# Sh.net
KiCad netlist of a schematic drawn in Altium Designer
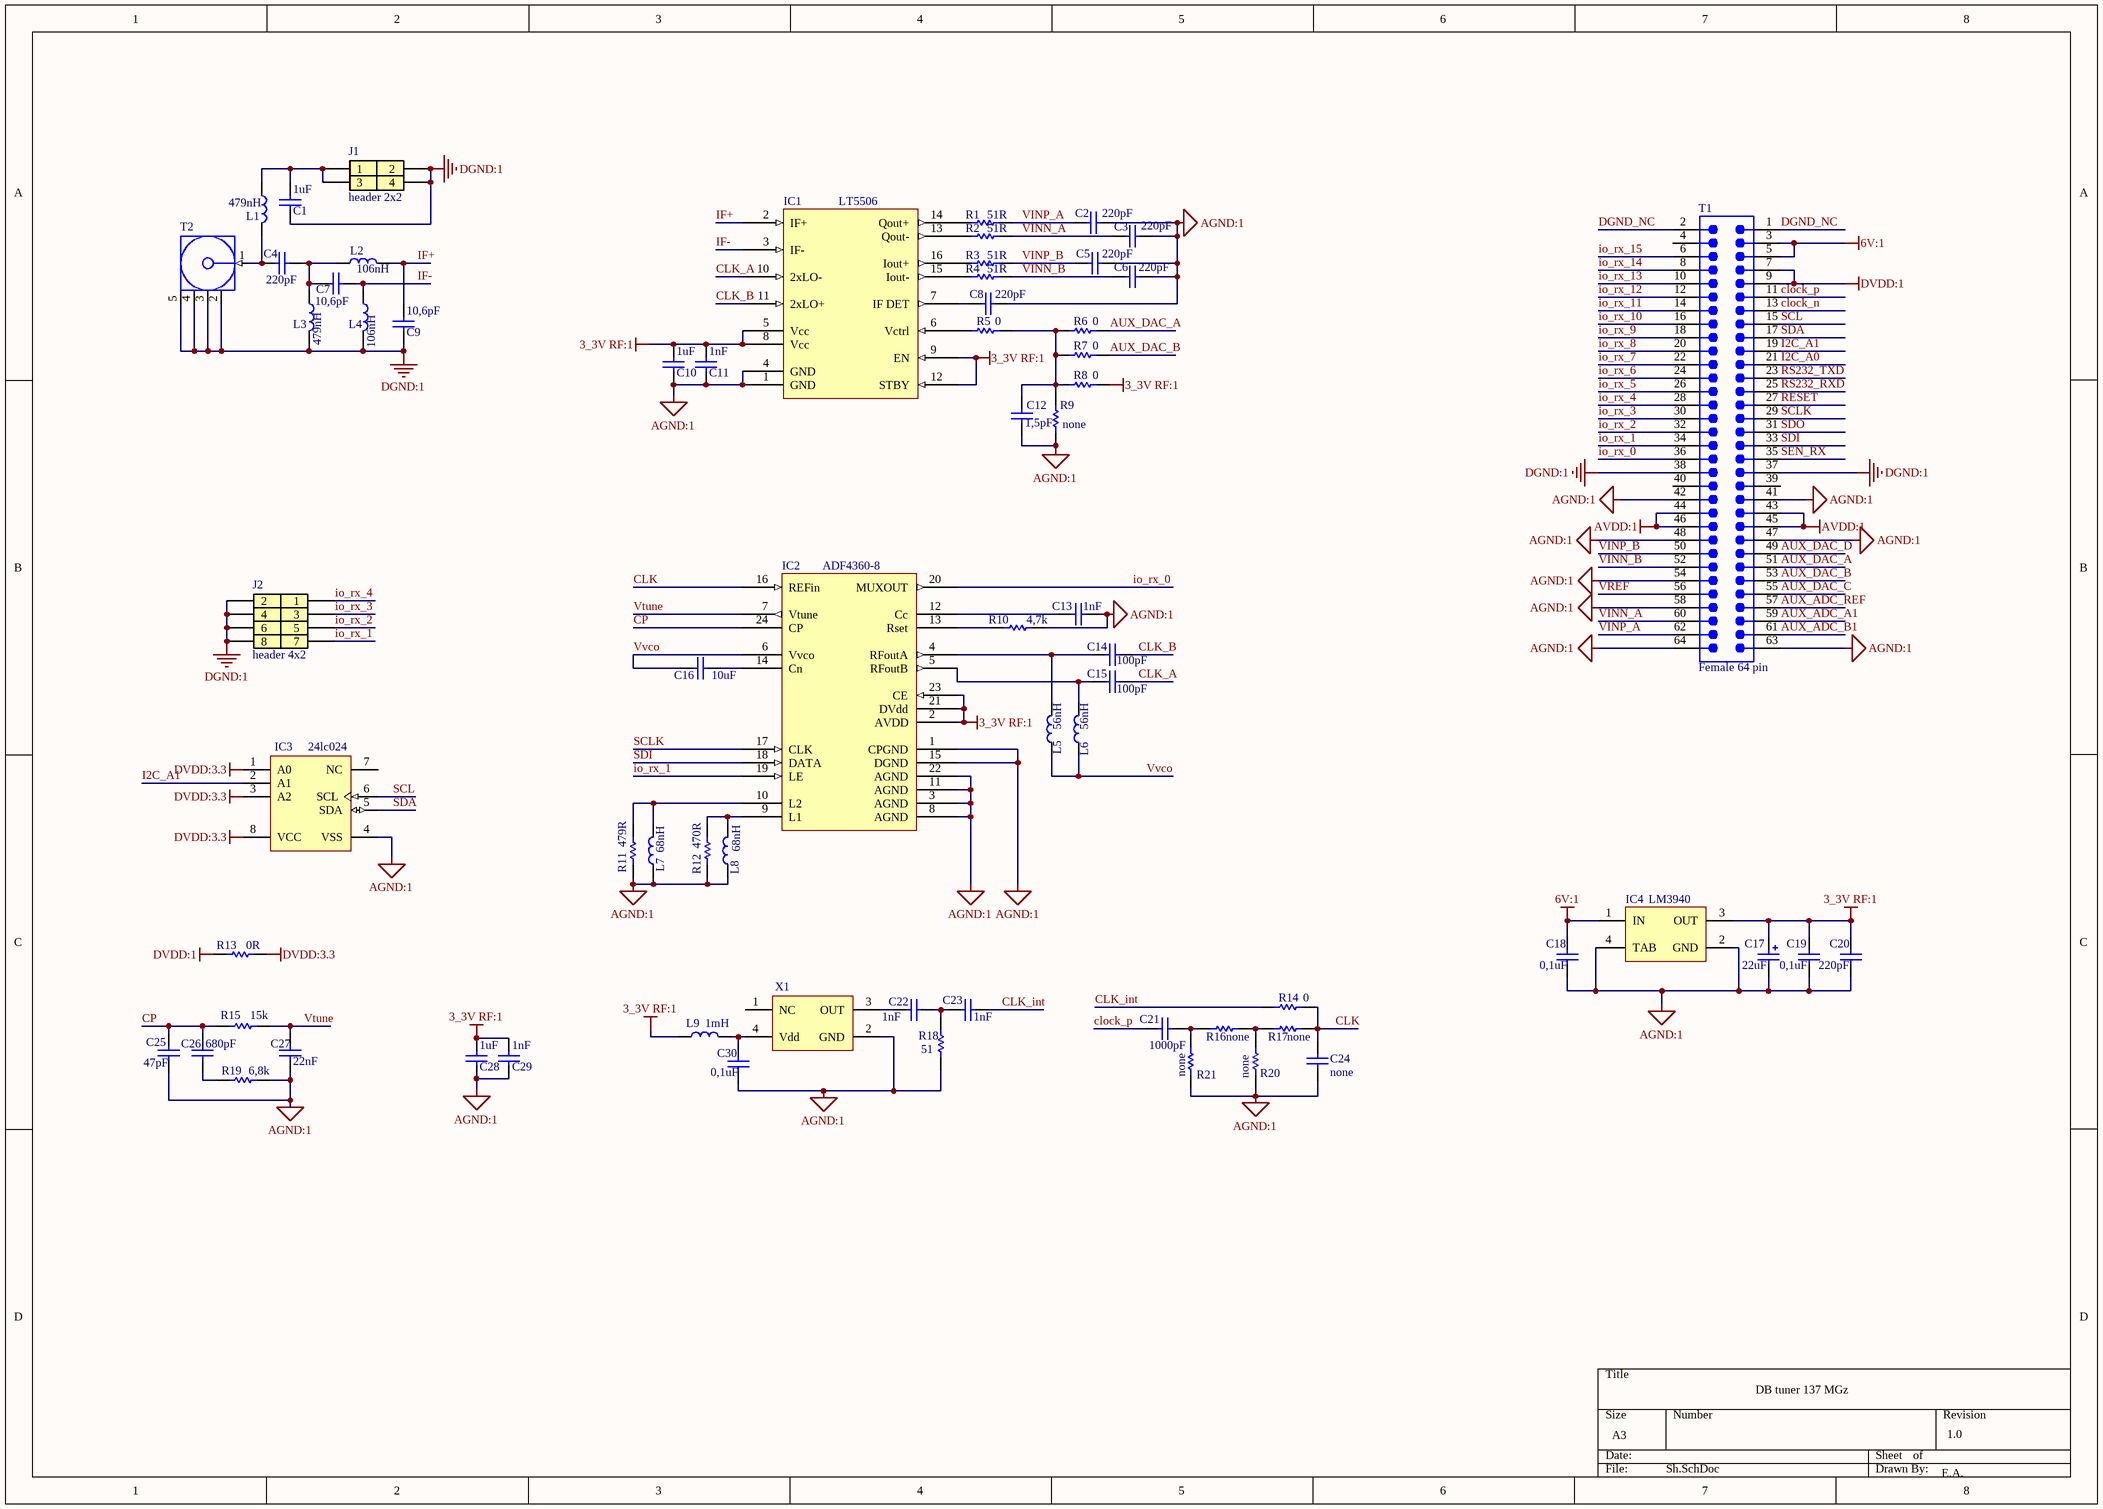
[diagram p0: Sh.SchDoc]

(export (version "E")
  (design (tool "Eeschema 10.0.6"))
  (components
    (comp (ref "C1") (value "1uF") (footprint "0805 cap") (libsource (lib "DB") (part "ceramic capacitor")))
    (comp (ref "C2") (value "220pF") (footprint "0805 cap") (libsource (lib "DB") (part "ceramic capacitor")))
    (comp (ref "C3") (value "220pF") (footprint "0805 cap") (libsource (lib "DB") (part "ceramic capacitor")))
    (comp (ref "C4") (value "220pF") (footprint "0805 cap") (libsource (lib "DB") (part "ceramic capacitor")))
    (comp (ref "C5") (value "220pF") (footprint "0805 cap") (libsource (lib "DB") (part "ceramic capacitor")))
    (comp (ref "C6") (value "220pF") (footprint "0805 cap") (libsource (lib "DB") (part "ceramic capacitor")))
    (comp (ref "C7")
      (value "10,6pF")
      (footprint "0805 cap")
      (libsource (lib "DB") (part "ceramic capacitor"))
    )
    (comp (ref "C8") (value "220pF") (footprint "0805 cap") (libsource (lib "DB") (part "ceramic capacitor")))
    (comp (ref "C9")
      (value "10,6pF")
      (footprint "0805 cap")
      (libsource (lib "DB") (part "ceramic capacitor"))
    )
    (comp (ref "C10") (value "1uF") (footprint "0805 cap") (libsource (lib "DB") (part "ceramic capacitor")))
    (comp (ref "C11") (value "1nF") (footprint "0805 cap") (libsource (lib "DB") (part "ceramic capacitor")))
    (comp (ref "C12")
      (value "1,5pF")
      (footprint "0805 cap")
      (libsource (lib "DB") (part "ceramic capacitor"))
    )
    (comp (ref "C13") (value "1nF") (footprint "0805 cap") (libsource (lib "DB") (part "ceramic capacitor")))
    (comp (ref "C14")
      (value "100pF")
      (footprint "0805 cap")
      (libsource (lib "DB") (part "ceramic capacitor"))
    )
    (comp (ref "C15")
      (value "100pF")
      (footprint "0805 cap")
      (libsource (lib "DB") (part "ceramic capacitor"))
    )
    (comp (ref "C16") (value "10uF") (footprint "0805 cap") (libsource (lib "DB") (part "ceramic capacitor")))
    (comp (ref "C17")
      (value "22uF")
      (footprint "capacitor C")
      (libsource (lib "DB") (part "tantalum capacitor"))
    )
    (comp (ref "C18")
      (value "0,1uF")
      (footprint "0805 cap")
      (libsource (lib "DB") (part "ceramic capacitor"))
    )
    (comp (ref "C19")
      (value "0,1uF")
      (footprint "0805 cap")
      (libsource (lib "DB") (part "ceramic capacitor"))
    )
    (comp (ref "C20")
      (value "220pF")
      (footprint "0805 cap")
      (libsource (lib "DB") (part "ceramic capacitor"))
    )
    (comp (ref "C21")
      (value "1000pF")
      (footprint "0805 cap")
      (libsource (lib "DB") (part "ceramic capacitor"))
    )
    (comp (ref "C22") (value "1nF") (footprint "0805 cap") (libsource (lib "DB") (part "ceramic capacitor")))
    (comp (ref "C23") (value "1nF") (footprint "0805 cap") (libsource (lib "DB") (part "ceramic capacitor")))
    (comp (ref "C24") (value "none") (footprint "0805 cap") (libsource (lib "DB") (part "ceramic capacitor")))
    (comp (ref "C25") (value "47pF") (footprint "0805 cap") (libsource (lib "DB") (part "ceramic capacitor")))
    (comp (ref "C26")
      (value "680pF")
      (footprint "0805 cap")
      (libsource (lib "DB") (part "ceramic capacitor"))
    )
    (comp (ref "C27") (value "22nF") (footprint "0805 cap") (libsource (lib "DB") (part "ceramic capacitor")))
    (comp (ref "C28") (value "1uF") (footprint "0805 cap") (libsource (lib "DB") (part "ceramic capacitor")))
    (comp (ref "C29") (value "1nF") (footprint "0805 cap") (libsource (lib "DB") (part "ceramic capacitor")))
    (comp (ref "C30")
      (value "0,1uF")
      (footprint "0805 cap")
      (libsource (lib "DB") (part "ceramic capacitor"))
    )
    (comp (ref "IC1")
      (value "LT5506")
      (footprint "QFN65P400X400X80-16N")
      (description "40MHz to 500MHz  Quadrature Demodulator  with VGA")
      (libsource (lib "DB") (part "LT5506"))
    )
    (comp (ref "IC2")
      (value "ADF4360-8")
      (footprint "QFN50P408X408X100-24N")
      (description "Integrated Synthesizer and VCO")
      (libsource (lib "DB") (part "ADF4360-8"))
    )
    (comp (ref "IC3") (value "24lc024") (footprint "SOIC_SN8") (libsource (lib "DB") (part "24lc024")))
    (comp (ref "IC4") (value "LM3940") (footprint "TO-263") (libsource (lib "DB") (part "LM3940")))
    (comp (ref "J1") (value "header 2x2") (footprint "pld 2x2") (libsource (lib "DB") (part "header 2x2")))
    (comp (ref "J2") (value "header 4x2") (footprint "H_4x2") (libsource (lib "DB") (part "header 4x2")))
    (comp (ref "L1") (value "479nH") (footprint "inductor 0805") (libsource (lib "DB") (part "inductor")))
    (comp (ref "L2") (value "106nH") (footprint "inductor 0805") (libsource (lib "") (part "inductor_1")))
    (comp (ref "L3") (value "479nH") (footprint "inductor 0805") (libsource (lib "DB") (part "inductor")))
    (comp (ref "L4") (value "106nH") (footprint "inductor 0805") (libsource (lib "DB") (part "inductor")))
    (comp (ref "L5") (value "56nH") (footprint "inductor 0805") (libsource (lib "DB") (part "inductor")))
    (comp (ref "L6") (value "56nH") (footprint "inductor 0805") (libsource (lib "DB") (part "inductor")))
    (comp (ref "L7") (value "68nH") (footprint "inductor 0805") (libsource (lib "DB") (part "inductor")))
    (comp (ref "L8") (value "68nH") (footprint "inductor 0805") (libsource (lib "DB") (part "inductor")))
    (comp (ref "L9") (value "1mH") (footprint "inductor 0805") (libsource (lib "") (part "inductor_1")))
    (comp (ref "R1") (value "51R") (footprint "0805 resistor") (libsource (lib "DB") (part "resistor")))
    (comp (ref "R2") (value "51R") (footprint "0805 resistor") (libsource (lib "DB") (part "resistor")))
    (comp (ref "R3") (value "51R") (footprint "0805 resistor") (libsource (lib "DB") (part "resistor")))
    (comp (ref "R4") (value "51R") (footprint "0805 resistor") (libsource (lib "DB") (part "resistor")))
    (comp (ref "R5") (value "0") (footprint "0805 resistor") (libsource (lib "DB") (part "resistor")))
    (comp (ref "R6") (value "0") (footprint "0805 resistor") (libsource (lib "DB") (part "resistor")))
    (comp (ref "R7") (value "0") (footprint "0805 resistor") (libsource (lib "DB") (part "resistor")))
    (comp (ref "R8") (value "0") (footprint "0805 resistor") (libsource (lib "DB") (part "resistor")))
    (comp (ref "R9") (value "none") (footprint "0805 resistor") (libsource (lib "DB") (part "resistor")))
    (comp (ref "R10") (value "4,7k") (footprint "0805 resistor") (libsource (lib "DB") (part "resistor")))
    (comp (ref "R11") (value "479R") (footprint "0805 resistor") (libsource (lib "DB") (part "resistor")))
    (comp (ref "R12") (value "470R") (footprint "0805 resistor") (libsource (lib "DB") (part "resistor")))
    (comp (ref "R13") (value "0R") (footprint "0805 resistor") (libsource (lib "DB") (part "resistor")))
    (comp (ref "R14") (value "0") (footprint "0805 resistor") (libsource (lib "DB") (part "resistor")))
    (comp (ref "R15") (value "15k") (footprint "0805 resistor") (libsource (lib "DB") (part "resistor")))
    (comp (ref "R16") (value "none") (footprint "0805 resistor") (libsource (lib "DB") (part "resistor")))
    (comp (ref "R17") (value "none") (footprint "0805 resistor") (libsource (lib "DB") (part "resistor")))
    (comp (ref "R18") (value "51") (footprint "0805 resistor") (libsource (lib "DB") (part "resistor")))
    (comp (ref "R19") (value "6,8k") (footprint "0805 resistor") (libsource (lib "DB") (part "resistor")))
    (comp (ref "R20") (value "none") (footprint "0805 resistor") (libsource (lib "DB") (part "resistor")))
    (comp (ref "R21") (value "none") (footprint "0805 resistor") (libsource (lib "DB") (part "resistor")))
    (comp (ref "T1")
      (value "Female 64 pin")
      (footprint "64pin female Mezzanine")
      (libsource (lib "DB") (part "Female 64 pin"))
    )
    (comp (ref "T2") (value "mcx_connect") (footprint "mcx_ra") (libsource (lib "DB") (part "mcx_connect")))
    (comp (ref "X1") (value "vcxo") (footprint "CLOCK OSCILLATOR") (libsource (lib "DB") (part "vcxo")))
  )
  (nets
    (net (code "1") (name "/AUX_ADC_A1") (class "Default")
      (node (ref "T1") (pin "59") (pinfunction "59_59") (pintype "passive"))
    )
    (net (code "2") (name "/AUX_ADC_B1") (class "Default")
      (node (ref "T1") (pin "61") (pinfunction "61_61") (pintype "passive"))
    )
    (net (code "3") (name "/AUX_ADC_REF") (class "Default")
      (node (ref "T1") (pin "57") (pinfunction "57_57") (pintype "passive"))
    )
    (net (code "4") (name "/AUX_DAC_A") (class "Default")
      (node (ref "R6") (pin "2") (pinfunction "2_2") (pintype "passive"))
      (node (ref "T1") (pin "51") (pinfunction "51_51") (pintype "passive"))
    )
    (net (code "5") (name "/AUX_DAC_B") (class "Default")
      (node (ref "R7") (pin "2") (pinfunction "2_2") (pintype "passive"))
      (node (ref "T1") (pin "53") (pinfunction "53_53") (pintype "passive"))
    )
    (net (code "6") (name "/AUX_DAC_C") (class "Default")
      (node (ref "T1") (pin "55") (pinfunction "55_55") (pintype "passive"))
    )
    (net (code "7") (name "/AUX_DAC_D") (class "Default")
      (node (ref "T1") (pin "49") (pinfunction "49_49") (pintype "passive"))
    )
    (net (code "8") (name "/CLK") (class "Default")
      (node (ref "C24") (pin "2") (pinfunction "2_2") (pintype "passive"))
      (node (ref "IC2") (pin "16") (pinfunction "REFin_16") (pintype "input"))
      (node (ref "R14") (pin "2") (pinfunction "2_2") (pintype "passive"))
      (node (ref "R17") (pin "1") (pinfunction "1_1") (pintype "passive"))
    )
    (net (code "9") (name "/CLK_A") (class "Default")
      (node (ref "C15") (pin "1") (pinfunction "1_1") (pintype "passive"))
      (node (ref "IC1") (pin "10") (pinfunction "2xLO-_10") (pintype "input"))
    )
    (net (code "10") (name "/CLK_B") (class "Default")
      (node (ref "C14") (pin "1") (pinfunction "1_1") (pintype "passive"))
      (node (ref "IC1") (pin "11") (pinfunction "2xLO+_11") (pintype "input"))
    )
    (net (code "11") (name "/CLK_int") (class "Default")
      (node (ref "C23") (pin "2") (pinfunction "2_2") (pintype "passive"))
      (node (ref "R14") (pin "1") (pinfunction "1_1") (pintype "passive"))
    )
    (net (code "12") (name "/CP") (class "Default")
      (node (ref "C25") (pin "2") (pinfunction "2_2") (pintype "passive"))
      (node (ref "C26") (pin "2") (pinfunction "2_2") (pintype "passive"))
      (node (ref "IC2") (pin "24") (pinfunction "CP_24") (pintype "passive"))
      (node (ref "R15") (pin "1") (pinfunction "1_1") (pintype "passive"))
    )
    (net (code "13") (name "/DGND_NC") (class "Default")
      (node (ref "T1") (pin "1") (pinfunction "1_1") (pintype "passive"))
      (node (ref "T1") (pin "2") (pinfunction "2_2") (pintype "passive"))
    )
    (net (code "14") (name "/I2C_A0") (class "Default")
      (node (ref "T1") (pin "21") (pinfunction "21_21") (pintype "passive"))
    )
    (net (code "15") (name "/I2C_A1") (class "Default")
      (node (ref "IC3") (pin "2") (pinfunction "A1_2") (pintype "passive"))
      (node (ref "T1") (pin "19") (pinfunction "19_19") (pintype "passive"))
    )
    (net (code "16") (name "/IF+") (class "Default")
      (node (ref "C9") (pin "2") (pinfunction "2_2") (pintype "passive"))
      (node (ref "IC1") (pin "2") (pinfunction "IF+_2") (pintype "input"))
      (node (ref "L2") (pin "2") (pinfunction "2_2") (pintype "passive"))
    )
    (net (code "17") (name "/IF-") (class "Default")
      (node (ref "C7") (pin "2") (pinfunction "2_2") (pintype "passive"))
      (node (ref "IC1") (pin "3") (pinfunction "IF-_3") (pintype "input"))
      (node (ref "L4") (pin "1") (pinfunction "1_1") (pintype "passive"))
    )
    (net (code "18") (name "/RESET") (class "Default")
      (node (ref "T1") (pin "27") (pinfunction "27_27") (pintype "passive"))
    )
    (net (code "19") (name "/RS232_RXD") (class "Default")
      (node (ref "T1") (pin "25") (pinfunction "25_25") (pintype "passive"))
    )
    (net (code "20") (name "/RS232_TXD") (class "Default")
      (node (ref "T1") (pin "23") (pinfunction "23_23") (pintype "passive"))
    )
    (net (code "21") (name "/SCL") (class "Default")
      (node (ref "IC3") (pin "6") (pinfunction "SCL_6") (pintype "input"))
      (node (ref "T1") (pin "15") (pinfunction "15_15") (pintype "passive"))
    )
    (net (code "22") (name "/SCLK") (class "Default")
      (node (ref "IC2") (pin "17") (pinfunction "CLK_17") (pintype "input"))
      (node (ref "T1") (pin "29") (pinfunction "29_29") (pintype "passive"))
    )
    (net (code "23") (name "/SDA") (class "Default")
      (node (ref "IC3") (pin "5") (pinfunction "SDA_5") (pintype "bidirectional"))
      (node (ref "T1") (pin "17") (pinfunction "17_17") (pintype "passive"))
    )
    (net (code "24") (name "/SDI") (class "Default")
      (node (ref "IC2") (pin "18") (pinfunction "DATA_18") (pintype "input"))
      (node (ref "T1") (pin "33") (pinfunction "33_33") (pintype "passive"))
    )
    (net (code "25") (name "/SDO") (class "Default")
      (node (ref "T1") (pin "31") (pinfunction "31_31") (pintype "passive"))
    )
    (net (code "26") (name "/SEN_RX") (class "Default")
      (node (ref "T1") (pin "35") (pinfunction "35_35") (pintype "passive"))
    )
    (net (code "27") (name "/VINN_A") (class "Default")
      (node (ref "C3") (pin "1") (pinfunction "1_1") (pintype "passive"))
      (node (ref "R2") (pin "2") (pinfunction "2_2") (pintype "passive"))
      (node (ref "T1") (pin "60") (pinfunction "60_60") (pintype "passive"))
    )
    (net (code "28") (name "/VINN_B") (class "Default")
      (node (ref "C6") (pin "1") (pinfunction "1_1") (pintype "passive"))
      (node (ref "R4") (pin "2") (pinfunction "2_2") (pintype "passive"))
      (node (ref "T1") (pin "52") (pinfunction "52_52") (pintype "passive"))
    )
    (net (code "29") (name "/VINP_A") (class "Default")
      (node (ref "C2") (pin "1") (pinfunction "1_1") (pintype "passive"))
      (node (ref "R1") (pin "2") (pinfunction "2_2") (pintype "passive"))
      (node (ref "T1") (pin "62") (pinfunction "62_62") (pintype "passive"))
    )
    (net (code "30") (name "/VINP_B") (class "Default")
      (node (ref "C5") (pin "1") (pinfunction "1_1") (pintype "passive"))
      (node (ref "R3") (pin "2") (pinfunction "2_2") (pintype "passive"))
      (node (ref "T1") (pin "50") (pinfunction "50_50") (pintype "passive"))
    )
    (net (code "31") (name "/VREF") (class "Default")
      (node (ref "T1") (pin "56") (pinfunction "56_56") (pintype "passive"))
    )
    (net (code "32") (name "/Vtune") (class "Default")
      (node (ref "C27") (pin "2") (pinfunction "2_2") (pintype "passive"))
      (node (ref "IC2") (pin "7") (pinfunction "Vtune_7") (pintype "output"))
      (node (ref "R15") (pin "2") (pinfunction "2_2") (pintype "passive"))
    )
    (net (code "33") (name "/Vvco") (class "Default")
      (node (ref "C16") (pin "1") (pinfunction "1_1") (pintype "passive"))
      (node (ref "IC2") (pin "6") (pinfunction "Vvco_6") (pintype "power_in"))
      (node (ref "L5") (pin "1") (pinfunction "1_1") (pintype "passive"))
      (node (ref "L6") (pin "1") (pinfunction "1_1") (pintype "passive"))
    )
    (net (code "34") (name "/clock_n") (class "Default")
      (node (ref "T1") (pin "13") (pinfunction "13_13") (pintype "passive"))
    )
    (net (code "35") (name "/clock_p") (class "Default")
      (node (ref "C21") (pin "1") (pinfunction "1_1") (pintype "passive"))
      (node (ref "T1") (pin "11") (pinfunction "11_11") (pintype "passive"))
    )
    (net (code "36") (name "/io_rx_0") (class "Default")
      (node (ref "IC2") (pin "20") (pinfunction "MUXOUT_20") (pintype "output"))
      (node (ref "T1") (pin "36") (pinfunction "36_36") (pintype "passive"))
    )
    (net (code "37") (name "/io_rx_1") (class "Default")
      (node (ref "IC2") (pin "19") (pinfunction "LE_19") (pintype "input"))
      (node (ref "J2") (pin "7") (pinfunction "7_7") (pintype "passive"))
      (node (ref "T1") (pin "34") (pinfunction "34_34") (pintype "passive"))
    )
    (net (code "38") (name "/io_rx_2") (class "Default")
      (node (ref "J2") (pin "5") (pinfunction "5_5") (pintype "passive"))
      (node (ref "T1") (pin "32") (pinfunction "32_32") (pintype "passive"))
    )
    (net (code "39") (name "/io_rx_3") (class "Default")
      (node (ref "J2") (pin "3") (pinfunction "3_3") (pintype "passive"))
      (node (ref "T1") (pin "30") (pinfunction "30_30") (pintype "passive"))
    )
    (net (code "40") (name "/io_rx_4") (class "Default")
      (node (ref "J2") (pin "1") (pinfunction "1_1") (pintype "passive"))
      (node (ref "T1") (pin "28") (pinfunction "28_28") (pintype "passive"))
    )
    (net (code "41") (name "/io_rx_5") (class "Default")
      (node (ref "T1") (pin "26") (pinfunction "26_26") (pintype "passive"))
    )
    (net (code "42") (name "/io_rx_6") (class "Default")
      (node (ref "T1") (pin "24") (pinfunction "24_24") (pintype "passive"))
    )
    (net (code "43") (name "/io_rx_7") (class "Default")
      (node (ref "T1") (pin "22") (pinfunction "22_22") (pintype "passive"))
    )
    (net (code "44") (name "/io_rx_8") (class "Default")
      (node (ref "T1") (pin "20") (pinfunction "20_20") (pintype "passive"))
    )
    (net (code "45") (name "/io_rx_9") (class "Default")
      (node (ref "T1") (pin "18") (pinfunction "18_18") (pintype "passive"))
    )
    (net (code "46") (name "/io_rx_10") (class "Default")
      (node (ref "T1") (pin "16") (pinfunction "16_16") (pintype "passive"))
    )
    (net (code "47") (name "/io_rx_11") (class "Default")
      (node (ref "T1") (pin "14") (pinfunction "14_14") (pintype "passive"))
    )
    (net (code "48") (name "/io_rx_12") (class "Default")
      (node (ref "T1") (pin "12") (pinfunction "12_12") (pintype "passive"))
    )
    (net (code "49") (name "/io_rx_13") (class "Default")
      (node (ref "T1") (pin "10") (pinfunction "10_10") (pintype "passive"))
    )
    (net (code "50") (name "/io_rx_14") (class "Default")
      (node (ref "T1") (pin "8") (pinfunction "8_8") (pintype "passive"))
    )
    (net (code "51") (name "/io_rx_15") (class "Default")
      (node (ref "T1") (pin "6") (pinfunction "6_6") (pintype "passive"))
    )
    (net (code "52") (name "3_3V RF:1") (class "Default")
      (node (ref "C10") (pin "2") (pinfunction "2_2") (pintype "passive"))
      (node (ref "C11") (pin "2") (pinfunction "2_2") (pintype "passive"))
      (node (ref "C17") (pin "1") (pinfunction "1_1") (pintype "passive"))
      (node (ref "C19") (pin "2") (pinfunction "2_2") (pintype "passive"))
      (node (ref "C20") (pin "2") (pinfunction "2_2") (pintype "passive"))
      (node (ref "C28") (pin "2") (pinfunction "2_2") (pintype "passive"))
      (node (ref "C29") (pin "2") (pinfunction "2_2") (pintype "passive"))
      (node (ref "IC1") (pin "12") (pinfunction "STBY_12") (pintype "input"))
      (node (ref "IC1") (pin "5") (pinfunction "Vcc_5") (pintype "power_in"))
      (node (ref "IC1") (pin "8") (pinfunction "Vcc_8") (pintype "power_in"))
      (node (ref "IC1") (pin "9") (pinfunction "EN_9") (pintype "input"))
      (node (ref "IC2") (pin "2") (pinfunction "AVDD_2") (pintype "power_in"))
      (node (ref "IC2") (pin "21") (pinfunction "DVdd_21") (pintype "power_in"))
      (node (ref "IC2") (pin "23") (pinfunction "CE_23") (pintype "input"))
      (node (ref "IC4") (pin "3") (pinfunction "OUT_3") (pintype "power_in"))
      (node (ref "L9") (pin "1") (pinfunction "1_1") (pintype "passive"))
      (node (ref "R8") (pin "2") (pinfunction "2_2") (pintype "passive"))
    )
    (net (code "53") (name "6V:1") (class "Default")
      (node (ref "C18") (pin "1") (pinfunction "1_1") (pintype "passive"))
      (node (ref "IC4") (pin "1") (pinfunction "IN_1") (pintype "power_in"))
      (node (ref "T1") (pin "3") (pinfunction "3_3") (pintype "passive"))
      (node (ref "T1") (pin "5") (pinfunction "5_5") (pintype "passive"))
    )
    (net (code "54") (name "AGND:1") (class "Default")
      (node (ref "C10") (pin "1") (pinfunction "1_1") (pintype "passive"))
      (node (ref "C11") (pin "1") (pinfunction "1_1") (pintype "passive"))
      (node (ref "C12") (pin "1") (pinfunction "1_1") (pintype "passive"))
      (node (ref "C13") (pin "1") (pinfunction "1_1") (pintype "passive"))
      (node (ref "C17") (pin "2") (pinfunction "2_2") (pintype "passive"))
      (node (ref "C18") (pin "2") (pinfunction "2_2") (pintype "passive"))
      (node (ref "C19") (pin "1") (pinfunction "1_1") (pintype "passive"))
      (node (ref "C2") (pin "2") (pinfunction "2_2") (pintype "passive"))
      (node (ref "C20") (pin "1") (pinfunction "1_1") (pintype "passive"))
      (node (ref "C24") (pin "1") (pinfunction "1_1") (pintype "passive"))
      (node (ref "C25") (pin "1") (pinfunction "1_1") (pintype "passive"))
      (node (ref "C27") (pin "1") (pinfunction "1_1") (pintype "passive"))
      (node (ref "C28") (pin "1") (pinfunction "1_1") (pintype "passive"))
      (node (ref "C29") (pin "1") (pinfunction "1_1") (pintype "passive"))
      (node (ref "C3") (pin "2") (pinfunction "2_2") (pintype "passive"))
      (node (ref "C30") (pin "1") (pinfunction "1_1") (pintype "passive"))
      (node (ref "C5") (pin "2") (pinfunction "2_2") (pintype "passive"))
      (node (ref "C6") (pin "2") (pinfunction "2_2") (pintype "passive"))
      (node (ref "C8") (pin "2") (pinfunction "2_2") (pintype "passive"))
      (node (ref "IC1") (pin "1") (pinfunction "GND_1") (pintype "power_in"))
      (node (ref "IC1") (pin "4") (pinfunction "GND_4") (pintype "power_in"))
      (node (ref "IC2") (pin "1") (pinfunction "CPGND_1") (pintype "power_in"))
      (node (ref "IC2") (pin "11") (pinfunction "AGND_11") (pintype "power_in"))
      (node (ref "IC2") (pin "15") (pinfunction "DGND_15") (pintype "power_in"))
      (node (ref "IC2") (pin "22") (pinfunction "AGND_22") (pintype "power_in"))
      (node (ref "IC2") (pin "3") (pinfunction "AGND_3") (pintype "power_in"))
      (node (ref "IC2") (pin "8") (pinfunction "AGND_8") (pintype "power_in"))
      (node (ref "IC3") (pin "4") (pinfunction "VSS_4") (pintype "power_in"))
      (node (ref "IC4") (pin "2") (pinfunction "GND_2") (pintype "power_in"))
      (node (ref "IC4") (pin "4") (pinfunction "TAB_4") (pintype "power_in"))
      (node (ref "L7") (pin "1") (pinfunction "1_1") (pintype "passive"))
      (node (ref "L8") (pin "1") (pinfunction "1_1") (pintype "passive"))
      (node (ref "R10") (pin "2") (pinfunction "2_2") (pintype "passive"))
      (node (ref "R11") (pin "1") (pinfunction "1_1") (pintype "passive"))
      (node (ref "R12") (pin "1") (pinfunction "1_1") (pintype "passive"))
      (node (ref "R18") (pin "1") (pinfunction "1_1") (pintype "passive"))
      (node (ref "R19") (pin "2") (pinfunction "2_2") (pintype "passive"))
      (node (ref "R20") (pin "1") (pinfunction "1_1") (pintype "passive"))
      (node (ref "R21") (pin "1") (pinfunction "1_1") (pintype "passive"))
      (node (ref "R9") (pin "1") (pinfunction "1_1") (pintype "passive"))
      (node (ref "T1") (pin "41") (pinfunction "41_41") (pintype "passive"))
      (node (ref "T1") (pin "42") (pinfunction "42_42") (pintype "passive"))
      (node (ref "T1") (pin "47") (pinfunction "47_47") (pintype "passive"))
      (node (ref "T1") (pin "48") (pinfunction "48_48") (pintype "passive"))
      (node (ref "T1") (pin "54") (pinfunction "54_54") (pintype "passive"))
      (node (ref "T1") (pin "58") (pinfunction "58_58") (pintype "passive"))
      (node (ref "T1") (pin "63") (pinfunction "63_63") (pintype "passive"))
      (node (ref "T1") (pin "64") (pinfunction "64_64") (pintype "passive"))
      (node (ref "X1") (pin "2") (pinfunction "GND_2") (pintype "power_in"))
    )
    (net (code "55") (name "AVDD:1") (class "Default")
      (node (ref "T1") (pin "43") (pinfunction "43_43") (pintype "passive"))
      (node (ref "T1") (pin "44") (pinfunction "44_44") (pintype "passive"))
      (node (ref "T1") (pin "45") (pinfunction "45_45") (pintype "passive"))
      (node (ref "T1") (pin "46") (pinfunction "46_46") (pintype "passive"))
    )
    (net (code "56") (name "DGND:1") (class "Default")
      (node (ref "C1") (pin "1") (pinfunction "1_1") (pintype "passive"))
      (node (ref "C9") (pin "1") (pinfunction "1_1") (pintype "passive"))
      (node (ref "J1") (pin "2") (pinfunction "2_2") (pintype "passive"))
      (node (ref "J1") (pin "4") (pinfunction "4_4") (pintype "passive"))
      (node (ref "J2") (pin "2") (pinfunction "2_2") (pintype "passive"))
      (node (ref "J2") (pin "4") (pinfunction "4_4") (pintype "passive"))
      (node (ref "J2") (pin "6") (pinfunction "6_6") (pintype "passive"))
      (node (ref "J2") (pin "8") (pinfunction "8_8") (pintype "passive"))
      (node (ref "L3") (pin "2") (pinfunction "2_2") (pintype "passive"))
      (node (ref "L4") (pin "2") (pinfunction "2_2") (pintype "passive"))
      (node (ref "T1") (pin "37") (pinfunction "37_37") (pintype "passive"))
      (node (ref "T1") (pin "38") (pinfunction "38_38") (pintype "passive"))
      (node (ref "T2") (pin "2") (pinfunction "GND_2") (pintype "power_in"))
      (node (ref "T2") (pin "3") (pinfunction "GND_3") (pintype "power_in"))
      (node (ref "T2") (pin "4") (pinfunction "GND_4") (pintype "power_in"))
      (node (ref "T2") (pin "5") (pinfunction "GND_5") (pintype "power_in"))
    )
    (net (code "57") (name "DVDD:1") (class "Default")
      (node (ref "R13") (pin "1") (pinfunction "1_1") (pintype "passive"))
      (node (ref "T1") (pin "7") (pinfunction "7_7") (pintype "passive"))
      (node (ref "T1") (pin "9") (pinfunction "9_9") (pintype "passive"))
    )
    (net (code "58") (name "DVDD:3.3") (class "Default")
      (node (ref "IC3") (pin "1") (pinfunction "A0_1") (pintype "passive"))
      (node (ref "IC3") (pin "3") (pinfunction "A2_3") (pintype "passive"))
      (node (ref "IC3") (pin "8") (pinfunction "VCC_8") (pintype "power_in"))
      (node (ref "R13") (pin "2") (pinfunction "2_2") (pintype "passive"))
    )
    (net (code "59") (name "Net-(C1-Pad2)") (class "Default")
      (node (ref "C1") (pin "2") (pinfunction "2_2") (pintype "passive"))
      (node (ref "J1") (pin "1") (pinfunction "1_1") (pintype "passive"))
      (node (ref "J1") (pin "3") (pinfunction "3_3") (pintype "passive"))
      (node (ref "L1") (pin "1") (pinfunction "1_1") (pintype "passive"))
    )
    (net (code "60") (name "Net-(C4-Pad2)") (class "Default")
      (node (ref "C4") (pin "2") (pinfunction "2_2") (pintype "passive"))
      (node (ref "C7") (pin "1") (pinfunction "1_1") (pintype "passive"))
      (node (ref "L2") (pin "1") (pinfunction "1_1") (pintype "passive"))
      (node (ref "L3") (pin "1") (pinfunction "1_1") (pintype "passive"))
    )
    (net (code "61") (name "Net-(C12-Pad2)") (class "Default")
      (node (ref "C12") (pin "2") (pinfunction "2_2") (pintype "passive"))
      (node (ref "R5") (pin "2") (pinfunction "2_2") (pintype "passive"))
      (node (ref "R6") (pin "1") (pinfunction "1_1") (pintype "passive"))
      (node (ref "R7") (pin "1") (pinfunction "1_1") (pintype "passive"))
      (node (ref "R8") (pin "1") (pinfunction "1_1") (pintype "passive"))
      (node (ref "R9") (pin "2") (pinfunction "2_2") (pintype "passive"))
    )
    (net (code "62") (name "Net-(C21-Pad2)") (class "Default")
      (node (ref "C21") (pin "2") (pinfunction "2_2") (pintype "passive"))
      (node (ref "R16") (pin "1") (pinfunction "1_1") (pintype "passive"))
      (node (ref "R21") (pin "2") (pinfunction "2_2") (pintype "passive"))
    )
    (net (code "63") (name "Net-(C22-Pad2)") (class "Default")
      (node (ref "C22") (pin "2") (pinfunction "2_2") (pintype "passive"))
      (node (ref "C23") (pin "1") (pinfunction "1_1") (pintype "passive"))
      (node (ref "R18") (pin "2") (pinfunction "2_2") (pintype "passive"))
    )
    (net (code "64") (name "Net-(C26-Pad1)") (class "Default")
      (node (ref "C26") (pin "1") (pinfunction "1_1") (pintype "passive"))
      (node (ref "R19") (pin "1") (pinfunction "1_1") (pintype "passive"))
    )
    (net (code "65") (name "Net-(IC1-IF_DET)") (class "Default")
      (node (ref "C8") (pin "1") (pinfunction "1_1") (pintype "passive"))
      (node (ref "IC1") (pin "7") (pinfunction "IF_DET_7") (pintype "output"))
    )
    (net (code "66") (name "Net-(IC1-Iout+)") (class "Default")
      (node (ref "IC1") (pin "16") (pinfunction "Iout+_16") (pintype "output"))
      (node (ref "R3") (pin "1") (pinfunction "1_1") (pintype "passive"))
    )
    (net (code "67") (name "Net-(IC1-Iout-)") (class "Default")
      (node (ref "IC1") (pin "15") (pinfunction "Iout-_15") (pintype "output"))
      (node (ref "R4") (pin "1") (pinfunction "1_1") (pintype "passive"))
    )
    (net (code "68") (name "Net-(IC1-Qout+)") (class "Default")
      (node (ref "IC1") (pin "14") (pinfunction "Qout+_14") (pintype "output"))
      (node (ref "R1") (pin "1") (pinfunction "1_1") (pintype "passive"))
    )
    (net (code "69") (name "Net-(IC1-Qout-)") (class "Default")
      (node (ref "IC1") (pin "13") (pinfunction "Qout-_13") (pintype "output"))
      (node (ref "R2") (pin "1") (pinfunction "1_1") (pintype "passive"))
    )
    (net (code "70") (name "Net-(IC1-Vctrl)") (class "Default")
      (node (ref "IC1") (pin "6") (pinfunction "Vctrl_6") (pintype "input"))
      (node (ref "R5") (pin "1") (pinfunction "1_1") (pintype "passive"))
    )
    (net (code "71") (name "Net-(IC2-Cc)") (class "Default")
      (node (ref "C13") (pin "2") (pinfunction "2_2") (pintype "passive"))
      (node (ref "IC2") (pin "12") (pinfunction "Cc_12") (pintype "passive"))
    )
    (net (code "72") (name "Net-(IC2-Cn)") (class "Default")
      (node (ref "C16") (pin "2") (pinfunction "2_2") (pintype "passive"))
      (node (ref "IC2") (pin "14") (pinfunction "Cn_14") (pintype "passive"))
    )
    (net (code "73") (name "Net-(IC2-L1)") (class "Default")
      (node (ref "IC2") (pin "9") (pinfunction "L1_9") (pintype "passive"))
      (node (ref "L8") (pin "2") (pinfunction "2_2") (pintype "passive"))
      (node (ref "R12") (pin "2") (pinfunction "2_2") (pintype "passive"))
    )
    (net (code "74") (name "Net-(IC2-L2)") (class "Default")
      (node (ref "IC2") (pin "10") (pinfunction "L2_10") (pintype "passive"))
      (node (ref "L7") (pin "2") (pinfunction "2_2") (pintype "passive"))
      (node (ref "R11") (pin "2") (pinfunction "2_2") (pintype "passive"))
    )
    (net (code "75") (name "Net-(IC2-RFoutA)") (class "Default")
      (node (ref "C14") (pin "2") (pinfunction "2_2") (pintype "passive"))
      (node (ref "IC2") (pin "4") (pinfunction "RFoutA_4") (pintype "output"))
      (node (ref "L5") (pin "2") (pinfunction "2_2") (pintype "passive"))
    )
    (net (code "76") (name "Net-(IC2-RFoutB)") (class "Default")
      (node (ref "C15") (pin "2") (pinfunction "2_2") (pintype "passive"))
      (node (ref "IC2") (pin "5") (pinfunction "RFoutB_5") (pintype "output"))
      (node (ref "L6") (pin "2") (pinfunction "2_2") (pintype "passive"))
    )
    (net (code "77") (name "Net-(IC2-Rset)") (class "Default")
      (node (ref "IC2") (pin "13") (pinfunction "Rset_13") (pintype "passive"))
      (node (ref "R10") (pin "1") (pinfunction "1_1") (pintype "passive"))
    )
    (net (code "78") (name "Net-(R16-Pad2)") (class "Default")
      (node (ref "R16") (pin "2") (pinfunction "2_2") (pintype "passive"))
      (node (ref "R17") (pin "2") (pinfunction "2_2") (pintype "passive"))
      (node (ref "R20") (pin "2") (pinfunction "2_2") (pintype "passive"))
    )
    (net (code "79") (name "Net-(T2-Signal)") (class "Default")
      (node (ref "C4") (pin "1") (pinfunction "1_1") (pintype "passive"))
      (node (ref "L1") (pin "2") (pinfunction "2_2") (pintype "passive"))
      (node (ref "T2") (pin "1") (pinfunction "Signal_1") (pintype "input"))
    )
    (net (code "80") (name "Net-(X1-OUT)") (class "Default")
      (node (ref "C22") (pin "1") (pinfunction "1_1") (pintype "passive"))
      (node (ref "X1") (pin "3") (pinfunction "OUT_3") (pintype "power_in"))
    )
    (net (code "81") (name "Net-(X1-Vdd)") (class "Default")
      (node (ref "C30") (pin "2") (pinfunction "2_2") (pintype "passive"))
      (node (ref "L9") (pin "2") (pinfunction "2_2") (pintype "passive"))
      (node (ref "X1") (pin "4") (pinfunction "Vdd_4") (pintype "power_in"))
    )
    (net (code "82") (name "unconnected-(IC3-NC-Pad7)") (class "Default")
      (node (ref "IC3") (pin "7") (pinfunction "NC_7") (pintype "passive"))
    )
    (net (code "83") (name "unconnected-(T1-Pad4)") (class "Default")
      (node (ref "T1") (pin "4") (pinfunction "4_4") (pintype "passive"))
    )
    (net (code "84") (name "unconnected-(T1-Pad39)") (class "Default")
      (node (ref "T1") (pin "39") (pinfunction "39_39") (pintype "passive"))
    )
    (net (code "85") (name "unconnected-(T1-Pad40)") (class "Default")
      (node (ref "T1") (pin "40") (pinfunction "40_40") (pintype "passive"))
    )
    (net (code "86") (name "unconnected-(X1-NC-Pad1)") (class "Default")
      (node (ref "X1") (pin "1") (pinfunction "NC_1") (pintype "power_in"))
    )
  )
)
